# TA_2.net
KiCad netlist of a schematic drawn in EAGLE
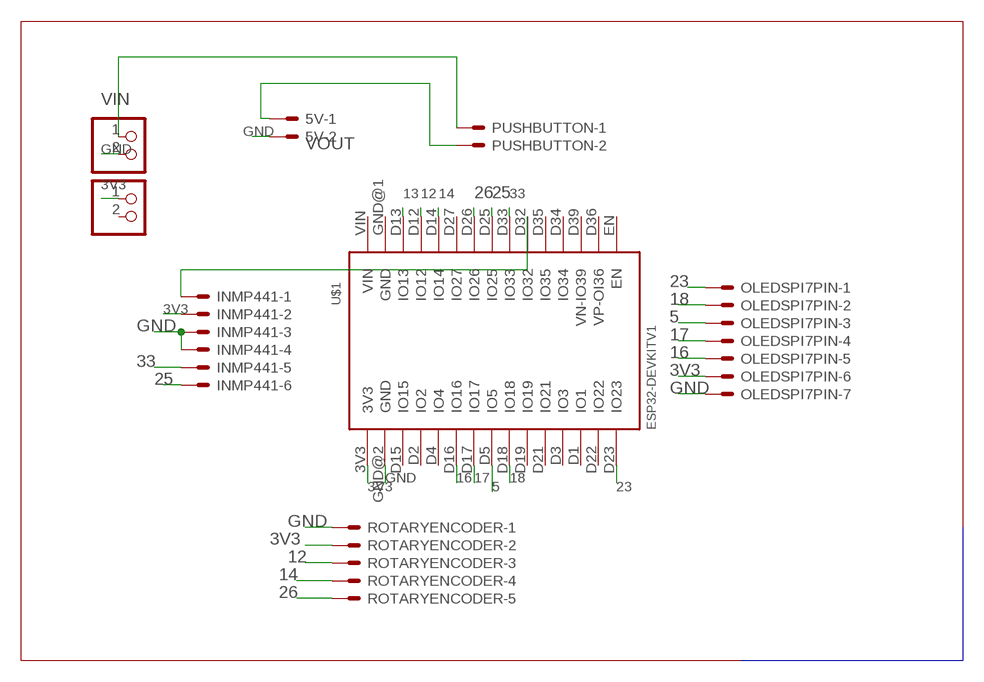
[diagram p0: schematic, sheet 1]

(export (version "E")
  (design (tool "Eeschema 10.0.6"))
  (components
    (comp (ref "5V")
      (value "JST-XH-02-PIN-LONG-PAD")
      (footprint "eagle-import:JST-XH-02-PACKAGE-LONG-PAD")
      (libsource (lib "eagle-import") (part "JST-XH-02-PIN-LONG-PAD"))
    )
    (comp (ref "INMP441")
      (value "JST-XH-06-PIN-LONG-PAD")
      (footprint "eagle-import:JST-XH-06-PACKAGE-LONG-PAD")
      (libsource (lib "eagle-import") (part "JST-XH-06-PIN-LONG-PAD"))
    )
    (comp (ref "OLEDSPI7PIN")
      (value "JST-XH-07-PIN-LONG-PAD")
      (footprint "eagle-import:JST-XH-07-PACKAGE-LONG-PAD")
      (libsource (lib "eagle-import") (part "JST-XH-07-PIN-LONG-PAD"))
    )
    (comp (ref "PUSHBUTTON")
      (value "JST-XH-02-PIN-LONG-PAD")
      (footprint "eagle-import:JST-XH-02-PACKAGE-LONG-PAD")
      (libsource (lib "eagle-import") (part "JST-XH-02-PIN-LONG-PAD"))
    )
    (comp (ref "ROTARYENCODER")
      (value "JST-XH-05-PIN-LONG-PAD")
      (footprint "eagle-import:JST-XH-05-PACKAGE-LONG-PAD")
      (libsource (lib "eagle-import") (part "JST-XH-05-PIN-LONG-PAD"))
    )
    (comp (ref "U$1")
      (value "ESP32DEVKITV1")
      (footprint "eagle-import:ESP32-DEVKITV1")
      (libsource (lib "eagle-import") (part "ESP32DEVKITV1"))
    )
    (comp (ref "VIN")
      (value "PINHD-1X2")
      (footprint "eagle-import:1X02")
      (libsource (lib "eagle-import") (part "PINHD-1X2"))
    )
    (comp (ref "VOUT")
      (value "PINHD-1X2")
      (footprint "eagle-import:1X02")
      (libsource (lib "eagle-import") (part "PINHD-1X2"))
    )
  )
  (nets
    (net (code "1") (name "/3V3") (class "Default")
      (node (ref "INMP441") (pin "2") (pinfunction "S_2") (pintype "passive"))
      (node (ref "OLEDSPI7PIN") (pin "6") (pinfunction "S_6") (pintype "passive"))
      (node (ref "ROTARYENCODER") (pin "2") (pinfunction "S_2") (pintype "passive"))
      (node (ref "U$1") (pin "3V3") (pinfunction "3V3_3V3") (pintype "bidirectional"))
      (node (ref "VOUT") (pin "1") (pinfunction "1_1") (pintype "passive"))
    )
    (net (code "2") (name "/5") (class "Default")
      (node (ref "OLEDSPI7PIN") (pin "3") (pinfunction "S_3") (pintype "passive"))
      (node (ref "U$1") (pin "D5") (pinfunction "IO5_D5") (pintype "bidirectional"))
    )
    (net (code "3") (name "/12") (class "Default")
      (node (ref "ROTARYENCODER") (pin "3") (pinfunction "S_3") (pintype "passive"))
      (node (ref "U$1") (pin "D12") (pinfunction "IO12_D12") (pintype "bidirectional"))
    )
    (net (code "4") (name "/13") (class "Default")
      (node (ref "U$1") (pin "D13") (pinfunction "IO13_D13") (pintype "bidirectional"))
    )
    (net (code "5") (name "/14") (class "Default")
      (node (ref "ROTARYENCODER") (pin "4") (pinfunction "S_4") (pintype "passive"))
      (node (ref "U$1") (pin "D14") (pinfunction "IO14_D14") (pintype "bidirectional"))
    )
    (net (code "6") (name "/16") (class "Default")
      (node (ref "OLEDSPI7PIN") (pin "5") (pinfunction "S_5") (pintype "passive"))
      (node (ref "U$1") (pin "D16") (pinfunction "IO16_D16") (pintype "bidirectional"))
    )
    (net (code "7") (name "/17") (class "Default")
      (node (ref "OLEDSPI7PIN") (pin "4") (pinfunction "S_4") (pintype "passive"))
      (node (ref "U$1") (pin "D17") (pinfunction "IO17_D17") (pintype "bidirectional"))
    )
    (net (code "8") (name "/18") (class "Default")
      (node (ref "OLEDSPI7PIN") (pin "2") (pinfunction "S_2") (pintype "passive"))
      (node (ref "U$1") (pin "D18") (pinfunction "IO18_D18") (pintype "bidirectional"))
    )
    (net (code "9") (name "/23") (class "Default")
      (node (ref "OLEDSPI7PIN") (pin "1") (pinfunction "S_1") (pintype "passive"))
      (node (ref "U$1") (pin "D23") (pinfunction "IO23_D23") (pintype "bidirectional"))
    )
    (net (code "10") (name "/25") (class "Default")
      (node (ref "INMP441") (pin "6") (pinfunction "S_6") (pintype "passive"))
      (node (ref "U$1") (pin "D25") (pinfunction "IO25_D25") (pintype "bidirectional"))
    )
    (net (code "11") (name "/26") (class "Default")
      (node (ref "ROTARYENCODER") (pin "5") (pinfunction "S_5") (pintype "passive"))
      (node (ref "U$1") (pin "D26") (pinfunction "IO26_D26") (pintype "bidirectional"))
    )
    (net (code "12") (name "/33") (class "Default")
      (node (ref "INMP441") (pin "5") (pinfunction "S_5") (pintype "passive"))
      (node (ref "U$1") (pin "D33") (pinfunction "IO33_D33") (pintype "bidirectional"))
    )
    (net (code "13") (name "/GND") (class "Default")
      (node (ref "5V") (pin "2") (pinfunction "S_2") (pintype "passive"))
      (node (ref "INMP441") (pin "3") (pinfunction "S_3") (pintype "passive"))
      (node (ref "INMP441") (pin "4") (pinfunction "S_4") (pintype "passive"))
      (node (ref "OLEDSPI7PIN") (pin "7") (pinfunction "S_7") (pintype "passive"))
      (node (ref "ROTARYENCODER") (pin "1") (pinfunction "S_1") (pintype "passive"))
      (node (ref "U$1") (pin "GND@2") (pinfunction "GND_GND@2") (pintype "bidirectional"))
      (node (ref "VIN") (pin "2") (pinfunction "2_2") (pintype "passive"))
    )
    (net (code "14") (name "Net-(5VA-S)") (class "Default")
      (node (ref "5V") (pin "1") (pinfunction "S_1") (pintype "passive"))
      (node (ref "PUSHBUTTON") (pin "2") (pinfunction "S_2") (pintype "passive"))
    )
    (net (code "15") (name "Net-(INMP441A-S)") (class "Default")
      (node (ref "INMP441") (pin "1") (pinfunction "S_1") (pintype "passive"))
      (node (ref "U$1") (pin "D32") (pinfunction "IO32_D32") (pintype "bidirectional"))
    )
    (net (code "16") (name "Net-(PUSHBUTTONA-S)") (class "Default")
      (node (ref "PUSHBUTTON") (pin "1") (pinfunction "S_1") (pintype "passive"))
      (node (ref "VIN") (pin "1") (pinfunction "1_1") (pintype "passive"))
    )
    (net (code "17") (name "unconnected-(U$1-GND-PadGND@1)") (class "Default")
      (node (ref "U$1") (pin "GND@1") (pinfunction "GND_GND@1") (pintype "bidirectional"))
    )
    (net (code "18") (name "unconnected-(U$1-IO1-PadD1)") (class "Default")
      (node (ref "U$1") (pin "D1") (pinfunction "IO1_D1") (pintype "bidirectional"))
    )
    (net (code "19") (name "unconnected-(U$1-IO2-PadD2)") (class "Default")
      (node (ref "U$1") (pin "D2") (pinfunction "IO2_D2") (pintype "bidirectional"))
    )
    (net (code "20") (name "unconnected-(U$1-IO3-PadD3)") (class "Default")
      (node (ref "U$1") (pin "D3") (pinfunction "IO3_D3") (pintype "bidirectional"))
    )
    (net (code "21") (name "unconnected-(U$1-IO4-PadD4)") (class "Default")
      (node (ref "U$1") (pin "D4") (pinfunction "IO4_D4") (pintype "bidirectional"))
    )
    (net (code "22") (name "unconnected-(U$1-IO15-PadD15)") (class "Default")
      (node (ref "U$1") (pin "D15") (pinfunction "IO15_D15") (pintype "bidirectional"))
    )
    (net (code "23") (name "unconnected-(U$1-IO19-PadD19)") (class "Default")
      (node (ref "U$1") (pin "D19") (pinfunction "IO19_D19") (pintype "bidirectional"))
    )
    (net (code "24") (name "unconnected-(U$1-IO21-PadD21)") (class "Default")
      (node (ref "U$1") (pin "D21") (pinfunction "IO21_D21") (pintype "bidirectional"))
    )
    (net (code "25") (name "unconnected-(U$1-IO22-PadD22)") (class "Default")
      (node (ref "U$1") (pin "D22") (pinfunction "IO22_D22") (pintype "bidirectional"))
    )
    (net (code "26") (name "unconnected-(U$1-IO27-PadD27)") (class "Default")
      (node (ref "U$1") (pin "D27") (pinfunction "IO27_D27") (pintype "bidirectional"))
    )
    (net (code "27") (name "unconnected-(U$1-IO34-PadD34)") (class "Default")
      (node (ref "U$1") (pin "D34") (pinfunction "IO34_D34") (pintype "bidirectional"))
    )
    (net (code "28") (name "unconnected-(U$1-IO35-PadD35)") (class "Default")
      (node (ref "U$1") (pin "D35") (pinfunction "IO35_D35") (pintype "bidirectional"))
    )
    (net (code "29") (name "unconnected-(U$1-PadEN)") (class "Default")
      (node (ref "U$1") (pin "EN") (pinfunction "EN_EN") (pintype "bidirectional"))
    )
    (net (code "30") (name "unconnected-(U$1-PadVIN)") (class "Default")
      (node (ref "U$1") (pin "VIN") (pinfunction "VIN_VIN") (pintype "bidirectional"))
    )
    (net (code "31") (name "unconnected-(U$1-VN-IO39-PadD39)") (class "Default")
      (node (ref "U$1") (pin "D39") (pinfunction "VN-IO39_D39") (pintype "bidirectional"))
    )
    (net (code "32") (name "unconnected-(U$1-VP-OI36-PadD36)") (class "Default")
      (node (ref "U$1") (pin "D36") (pinfunction "VP-OI36_D36") (pintype "bidirectional"))
    )
    (net (code "33") (name "unconnected-(VOUT-Pad2)") (class "Default")
      (node (ref "VOUT") (pin "2") (pinfunction "2_2") (pintype "passive"))
    )
  )
)
